# Sheet1.net
KiCad netlist of a schematic drawn in Altium Designer
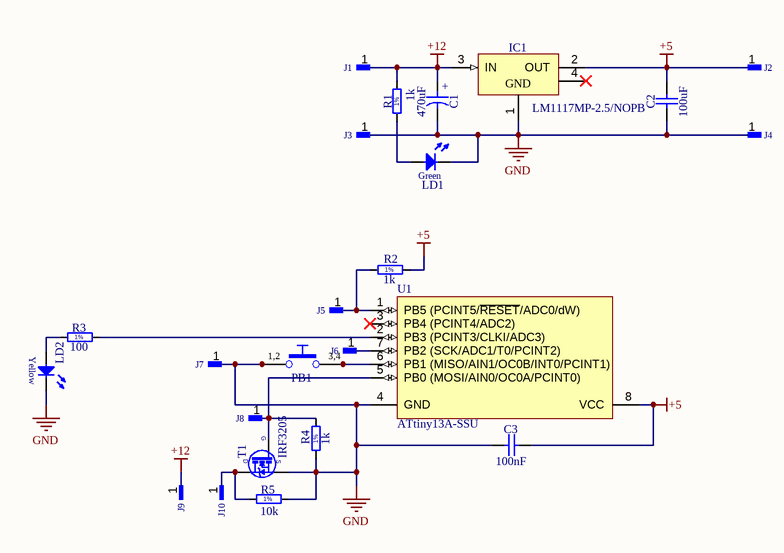
[diagram p0: Sheet1.SchDoc]

(export (version "E")
  (design (tool "Eeschema 10.0.6"))
  (components
    (comp (ref "C1")
      (value "470uF")
      (footprint "CAPPR500-1050X1150")
      (description "Polarised capacitor")
      (fields
        (field (name "PART NUMBER") "CAER_470UF_10V_20%_500-1050X1150_LESR0R015")
        (field (name "VOLTAGE") "10V")
        (field (name "AUTHOR") "CERN DEM JLC")
      )
      (libsource (lib "Capacitors") (part "Capacitor - polarized"))
    )
    (comp (ref "C2")
      (value "100uF")
      (footprint "CAPC3216X180N")
      (description "Non-polarised capacitor")
      (fields
        (field (name "PART NUMBER") "CC1206_100UF_6.3V_20%_X5R")
        (field (name "VOLTAGE") "6.3V")
        (field (name "AUTHOR") "CERN DEM JLC")
      )
      (libsource (lib "Capacitors") (part "Capacitor - non polarized"))
    )
    (comp (ref "C3")
      (value "100nF")
      (footprint "CAPC2012X135N")
      (description "Non-polarised capacitor")
      (fields
        (field (name "PART NUMBER") "CC0805_100NF_50V_10%_X7R")
        (field (name "VOLTAGE") "50V")
        (field (name "AUTHOR") "CERN DEM JLC")
      )
      (libsource (lib "Capacitors") (part "Capacitor - non polarized"))
    )
    (comp (ref "IC1")
      (value "LM1117MP-2.5/NOPB")
      (footprint "SOT230P700X180-4N")
      (description "3-Terminal Regulator 1=GND 2=OUT 3=IN 4=OUT")
      (fields (field (name "MANUFACTURER") "TEXAS INSTRUMENTS") (field (name "AUTHOR") "CERN DEM JLC"))
      (libsource (lib "ICs And Semiconductors") (part "REG3+1 1GND-2OUT-3IN+4OUT"))
    )
    (comp (ref "J1")
      (value "SMD Pad")
      (footprint "R400X300")
      (description "Single SMD Pad")
      (fields (field (name "PART NUMBER") "SMD_PAD_4X3MM") (field (name "AUTHOR") "CERN DEM JLC"))
      (libsource (lib "Eletro-mechanical") (part "Single SMD Pad"))
    )
    (comp (ref "J2")
      (value "SMD Pad")
      (footprint "R400X300")
      (description "Single SMD Pad")
      (fields (field (name "PART NUMBER") "SMD_PAD_4X3MM") (field (name "AUTHOR") "CERN DEM JLC"))
      (libsource (lib "") (part "Single SMD Pad_1"))
    )
    (comp (ref "J3")
      (value "SMD Pad")
      (footprint "R400X300")
      (description "Single SMD Pad")
      (fields (field (name "PART NUMBER") "SMD_PAD_4X3MM") (field (name "AUTHOR") "CERN DEM JLC"))
      (libsource (lib "Eletro-mechanical") (part "Single SMD Pad"))
    )
    (comp (ref "J4")
      (value "SMD Pad")
      (footprint "R400X300")
      (description "Single SMD Pad")
      (fields (field (name "PART NUMBER") "SMD_PAD_4X3MM") (field (name "AUTHOR") "CERN DEM JLC"))
      (libsource (lib "") (part "Single SMD Pad_1"))
    )
    (comp (ref "J5")
      (value "SMD Pad")
      (footprint "R350X200")
      (description "Single SMD Pad")
      (fields (field (name "PART NUMBER") "SMD_PAD_3.5X2MM") (field (name "AUTHOR") "CERN DEM JLC"))
      (libsource (lib "Eletro-mechanical") (part "Single SMD Pad"))
    )
    (comp (ref "J6")
      (value "SMD Pad")
      (footprint "R400X300")
      (description "Single SMD Pad")
      (fields (field (name "PART NUMBER") "SMD_PAD_4X3MM") (field (name "AUTHOR") "CERN DEM JLC"))
      (libsource (lib "Eletro-mechanical") (part "Single SMD Pad"))
    )
    (comp (ref "J7")
      (value "SMD Pad")
      (footprint "R350X200")
      (description "Single SMD Pad")
      (fields (field (name "PART NUMBER") "SMD_PAD_3.5X2MM") (field (name "AUTHOR") "CERN DEM JLC"))
      (libsource (lib "Eletro-mechanical") (part "Single SMD Pad"))
    )
    (comp (ref "J8")
      (value "SMD Pad")
      (footprint "R350X200")
      (description "Single SMD Pad")
      (fields (field (name "PART NUMBER") "SMD_PAD_3.5X2MM") (field (name "AUTHOR") "CERN DEM JLC"))
      (libsource (lib "Eletro-mechanical") (part "Single SMD Pad"))
    )
    (comp (ref "J9")
      (value "SMD Pad")
      (footprint "R400X300")
      (description "Single SMD Pad")
      (fields (field (name "PART NUMBER") "SMD_PAD_4X3MM") (field (name "AUTHOR") "CERN DEM JLC"))
      (libsource (lib "") (part "Single SMD Pad_2"))
    )
    (comp (ref "J10")
      (value "SMD Pad")
      (footprint "R400X300")
      (description "Single SMD Pad")
      (fields (field (name "PART NUMBER") "SMD_PAD_4X3MM") (field (name "AUTHOR") "CERN DEM JLC"))
      (libsource (lib "") (part "Single SMD Pad_2"))
    )
    (comp (ref "LD1")
      (value "Green")
      (footprint "LED_3MM_GREEN_1C-2A")
      (description "LED Green 1C 2A")
      (fields
        (field (name "PART NUMBER") "LED_AVAGO_HLMP-1790")
        (field (name "MANUFACTURER") "AVAGO TECHNOLOGIES")
        (field (name "AUTHOR") "CERN DEM JLC")
      )
      (libsource (lib "ICs And Semiconductors") (part "LED Green 1C 2A"))
    )
    (comp (ref "LD2")
      (value "Yellow")
      (footprint "LED_3MM_YELLOW_1C-2A")
      (description "LED Yellow 1C 2A")
      (fields
        (field (name "PART NUMBER") "LED_AVAGO_HLMP-1719")
        (field (name "MANUFACTURER") "AVAGO TECHNOLOGIES")
        (field (name "AUTHOR") "CERN DEM JLC")
      )
      (libsource (lib "ICs And Semiconductors") (part "LED Yellow 1C 2A"))
    )
    (comp (ref "PB1")
      (value "Push Button")
      (footprint "PB_ALPS_SKHHDTA010")
      (description "Push-Button Switch SPDT")
      (fields
        (field (name "PART NUMBER") "PB_ALPS_SKHHDTA010")
        (field (name "MANUFACTURER") "ALPS")
        (field (name "AUTHOR") "CERN DEM JLC")
      )
      (libsource (lib "Eletro-mechanical") (part "PB SPST 12NO-34NO"))
    )
    (comp (ref "R1")
      (value "1k")
      (footprint "RESC2012X60N")
      (description "Resistor - 1%")
      (fields
        (field (name "PART NUMBER") "R0805_1K_1%_0.33W_100PPM_VISHAY_CRCW-HP")
        (field (name "POWER") "0.33W")
        (field (name "AUTHOR") "CERN DEM JLC")
      )
      (libsource (lib "Resistors") (part "Resistor - 1%"))
    )
    (comp (ref "R2")
      (value "1k")
      (footprint "RESC2012X60N")
      (description "Resistor - 1%")
      (fields
        (field (name "PART NUMBER") "R0805_1K_1%_0.33W_100PPM_VISHAY_CRCW-HP")
        (field (name "POWER") "0.33W")
        (field (name "AUTHOR") "CERN DEM JLC")
      )
      (libsource (lib "Resistors") (part "Resistor - 1%"))
    )
    (comp (ref "R3")
      (value "100")
      (footprint "RESC2012X60N")
      (description "Resistor - 1%")
      (fields
        (field (name "PART NUMBER") "R0805_100R_1%_0.125W_100PPM")
        (field (name "POWER") "0.125W")
        (field (name "AUTHOR") "CERN DEM JLC")
      )
      (libsource (lib "Resistors") (part "Resistor - 1%"))
    )
    (comp (ref "R4")
      (value "1k")
      (footprint "RESC2012X60N")
      (description "Resistor - 1%")
      (fields
        (field (name "PART NUMBER") "R0805_1K_1%_0.33W_100PPM_VISHAY_CRCW-HP")
        (field (name "POWER") "0.33W")
        (field (name "AUTHOR") "CERN DEM JLC")
      )
      (libsource (lib "Resistors") (part "Resistor - 1%"))
    )
    (comp (ref "R5")
      (value "10k")
      (footprint "RESC2012X60N")
      (description "Resistor - 1%")
      (fields
        (field (name "PART NUMBER") "R0805_10K_1%_0.125W_100PPM")
        (field (name "POWER") "0.125W")
        (field (name "AUTHOR") "CERN DEM JLC")
      )
      (libsource (lib "Resistors") (part "Resistor - 1%"))
    )
    (comp (ref "T1")
      (value "IRF3205")
      (footprint "TO-220-V")
      (description "N-CHANNEL MOSFET WITH ZENER DIODE")
      (fields
        (field (name "PART NUMBER") "IRF640NPBF_v")
        (field (name "MANUFACTURER") "INTERNATIONAL RECTIFIER")
        (field (name "AUTHOR") "CERN DEM JLC")
      )
      (libsource (lib "ICs And Semiconductors") (part "N-MOSFET-DZ 1G 2D 3S"))
    )
    (comp (ref "U1")
      (value "ATtiny13A-SSU")
      (footprint "8S1_N")
      (fields (field (name "PUBLISHER") "Altium Limited"))
      (libsource (lib "Atmel Microcontroller 8-Bit tinyAVR") (part "ATtiny13A-SSU"))
    )
  )
  (nets
    (net (code "1") (name "+5") (class "Default")
      (node (ref "C2") (pin "2") (pinfunction "2_2") (pintype "passive"))
      (node (ref "C3") (pin "2") (pinfunction "2_2") (pintype "passive"))
      (node (ref "IC1") (pin "2") (pinfunction "OUT_2") (pintype "power_in"))
      (node (ref "J2") (pin "1") (pinfunction "1_1") (pintype "bidirectional"))
      (node (ref "R2") (pin "2") (pinfunction "2_2") (pintype "passive"))
      (node (ref "U1") (pin "8") (pinfunction "VCC_8") (pintype "power_in"))
    )
    (net (code "2") (name "+12") (class "Default")
      (node (ref "C1") (pin "1") (pinfunction "1_1") (pintype "passive"))
      (node (ref "IC1") (pin "3") (pinfunction "IN_3") (pintype "input"))
      (node (ref "J1") (pin "1") (pinfunction "1_1") (pintype "bidirectional"))
      (node (ref "J9") (pin "1") (pinfunction "1_1") (pintype "bidirectional"))
      (node (ref "R1") (pin "2") (pinfunction "2_2") (pintype "passive"))
    )
    (net (code "3") (name "GND") (class "Default")
      (node (ref "C1") (pin "2") (pinfunction "2_2") (pintype "passive"))
      (node (ref "C2") (pin "1") (pinfunction "1_1") (pintype "passive"))
      (node (ref "C3") (pin "1") (pinfunction "1_1") (pintype "passive"))
      (node (ref "IC1") (pin "1") (pinfunction "GND_1") (pintype "power_in"))
      (node (ref "J3") (pin "1") (pinfunction "1_1") (pintype "bidirectional"))
      (node (ref "J4") (pin "1") (pinfunction "1_1") (pintype "bidirectional"))
      (node (ref "J7") (pin "1") (pinfunction "1_1") (pintype "bidirectional"))
      (node (ref "LD1") (pin "1") (pinfunction "C_1") (pintype "passive"))
      (node (ref "LD2") (pin "1") (pinfunction "C_1") (pintype "passive"))
      (node (ref "PB1") (pin "1") (pinfunction "1_1") (pintype "passive"))
      (node (ref "PB1") (pin "2") (pinfunction "2_2") (pintype "passive"))
      (node (ref "R4") (pin "1") (pinfunction "1_1") (pintype "passive"))
      (node (ref "R5") (pin "2") (pinfunction "2_2") (pintype "passive"))
      (node (ref "T1") (pin "3") (pinfunction "S_3") (pintype "passive"))
      (node (ref "U1") (pin "4") (pinfunction "GND_4") (pintype "power_in"))
    )
    (net (code "4") (name "Net-(LD1-A)") (class "Default")
      (node (ref "LD1") (pin "2") (pinfunction "A_2") (pintype "passive"))
      (node (ref "R1") (pin "1") (pinfunction "1_1") (pintype "passive"))
    )
    (net (code "5") (name "Net-(LD2-A)") (class "Default")
      (node (ref "LD2") (pin "2") (pinfunction "A_2") (pintype "passive"))
      (node (ref "R3") (pin "1") (pinfunction "1_1") (pintype "passive"))
    )
    (net (code "6") (name "Net-(T1-D)") (class "Default")
      (node (ref "J10") (pin "1") (pinfunction "1_1") (pintype "bidirectional"))
      (node (ref "R5") (pin "1") (pinfunction "1_1") (pintype "passive"))
      (node (ref "T1") (pin "2") (pinfunction "D_2") (pintype "passive"))
    )
    (net (code "7") (name "Net-(T1-G)") (class "Default")
      (node (ref "J8") (pin "1") (pinfunction "1_1") (pintype "bidirectional"))
      (node (ref "R4") (pin "2") (pinfunction "2_2") (pintype "passive"))
      (node (ref "T1") (pin "1") (pinfunction "G_1") (pintype "passive"))
      (node (ref "U1") (pin "5") (pinfunction "PB0_(MOSI/AIN0/OC0A/PCINT0)_5") (pintype "bidirectional"))
    )
    (net (code "8") (name "Net-(U1-PB1_(MISO{slash}AIN1{slash}OC0B{slash}INT0{slash}PCINT1))") (class "Default")
      (node (ref "PB1") (pin "3") (pinfunction "3_3") (pintype "passive"))
      (node (ref "PB1") (pin "4") (pinfunction "4_4") (pintype "passive"))
      (node (ref "U1") (pin "6") (pinfunction "PB1_(MISO/AIN1/OC0B/INT0/PCINT1)_6") (pintype "bidirectional"))
    )
    (net (code "9") (name "Net-(U1-PB2_(SCK{slash}ADC1{slash}T0{slash}PCINT2))") (class "Default")
      (node (ref "J6") (pin "1") (pinfunction "1_1") (pintype "bidirectional"))
      (node (ref "U1") (pin "7") (pinfunction "PB2_(SCK/ADC1/T0/PCINT2)_7") (pintype "bidirectional"))
    )
    (net (code "10") (name "Net-(U1-PB3_(PCINT3{slash}CLKI{slash}ADC3))") (class "Default")
      (node (ref "R3") (pin "2") (pinfunction "2_2") (pintype "passive"))
      (node (ref "U1") (pin "2") (pinfunction "PB3_(PCINT3/CLKI/ADC3)_2") (pintype "bidirectional"))
    )
    (net (code "11") (name "Net-(U1-PB5_(PCINT5{slash}~{RESET}{slash}ADC0{slash}dW))") (class "Default")
      (node (ref "J5") (pin "1") (pinfunction "1_1") (pintype "bidirectional"))
      (node (ref "R2") (pin "1") (pinfunction "1_1") (pintype "passive"))
      (node (ref "U1") (pin "1") (pinfunction "PB5_(PCINT5/~{RESET}/ADC0/dW)_1") (pintype "bidirectional"))
    )
    (net (code "12") (name "unconnected-(IC1-OUT-Pad4)") (class "Default")
      (node (ref "IC1") (pin "4") (pinfunction "OUT_4") (pintype "power_in+no_connect"))
    )
    (net (code "13") (name "unconnected-(U1-PB4_(PCINT4{slash}ADC2)-Pad3)") (class "Default")
      (node (ref "U1") (pin "3") (pinfunction "PB4_(PCINT4/ADC2)_3") (pintype "bidirectional+no_connect"))
    )
  )
)
